# HD68_BNC_Breakout.net
KiCad netlist of a schematic drawn in Altium Designer
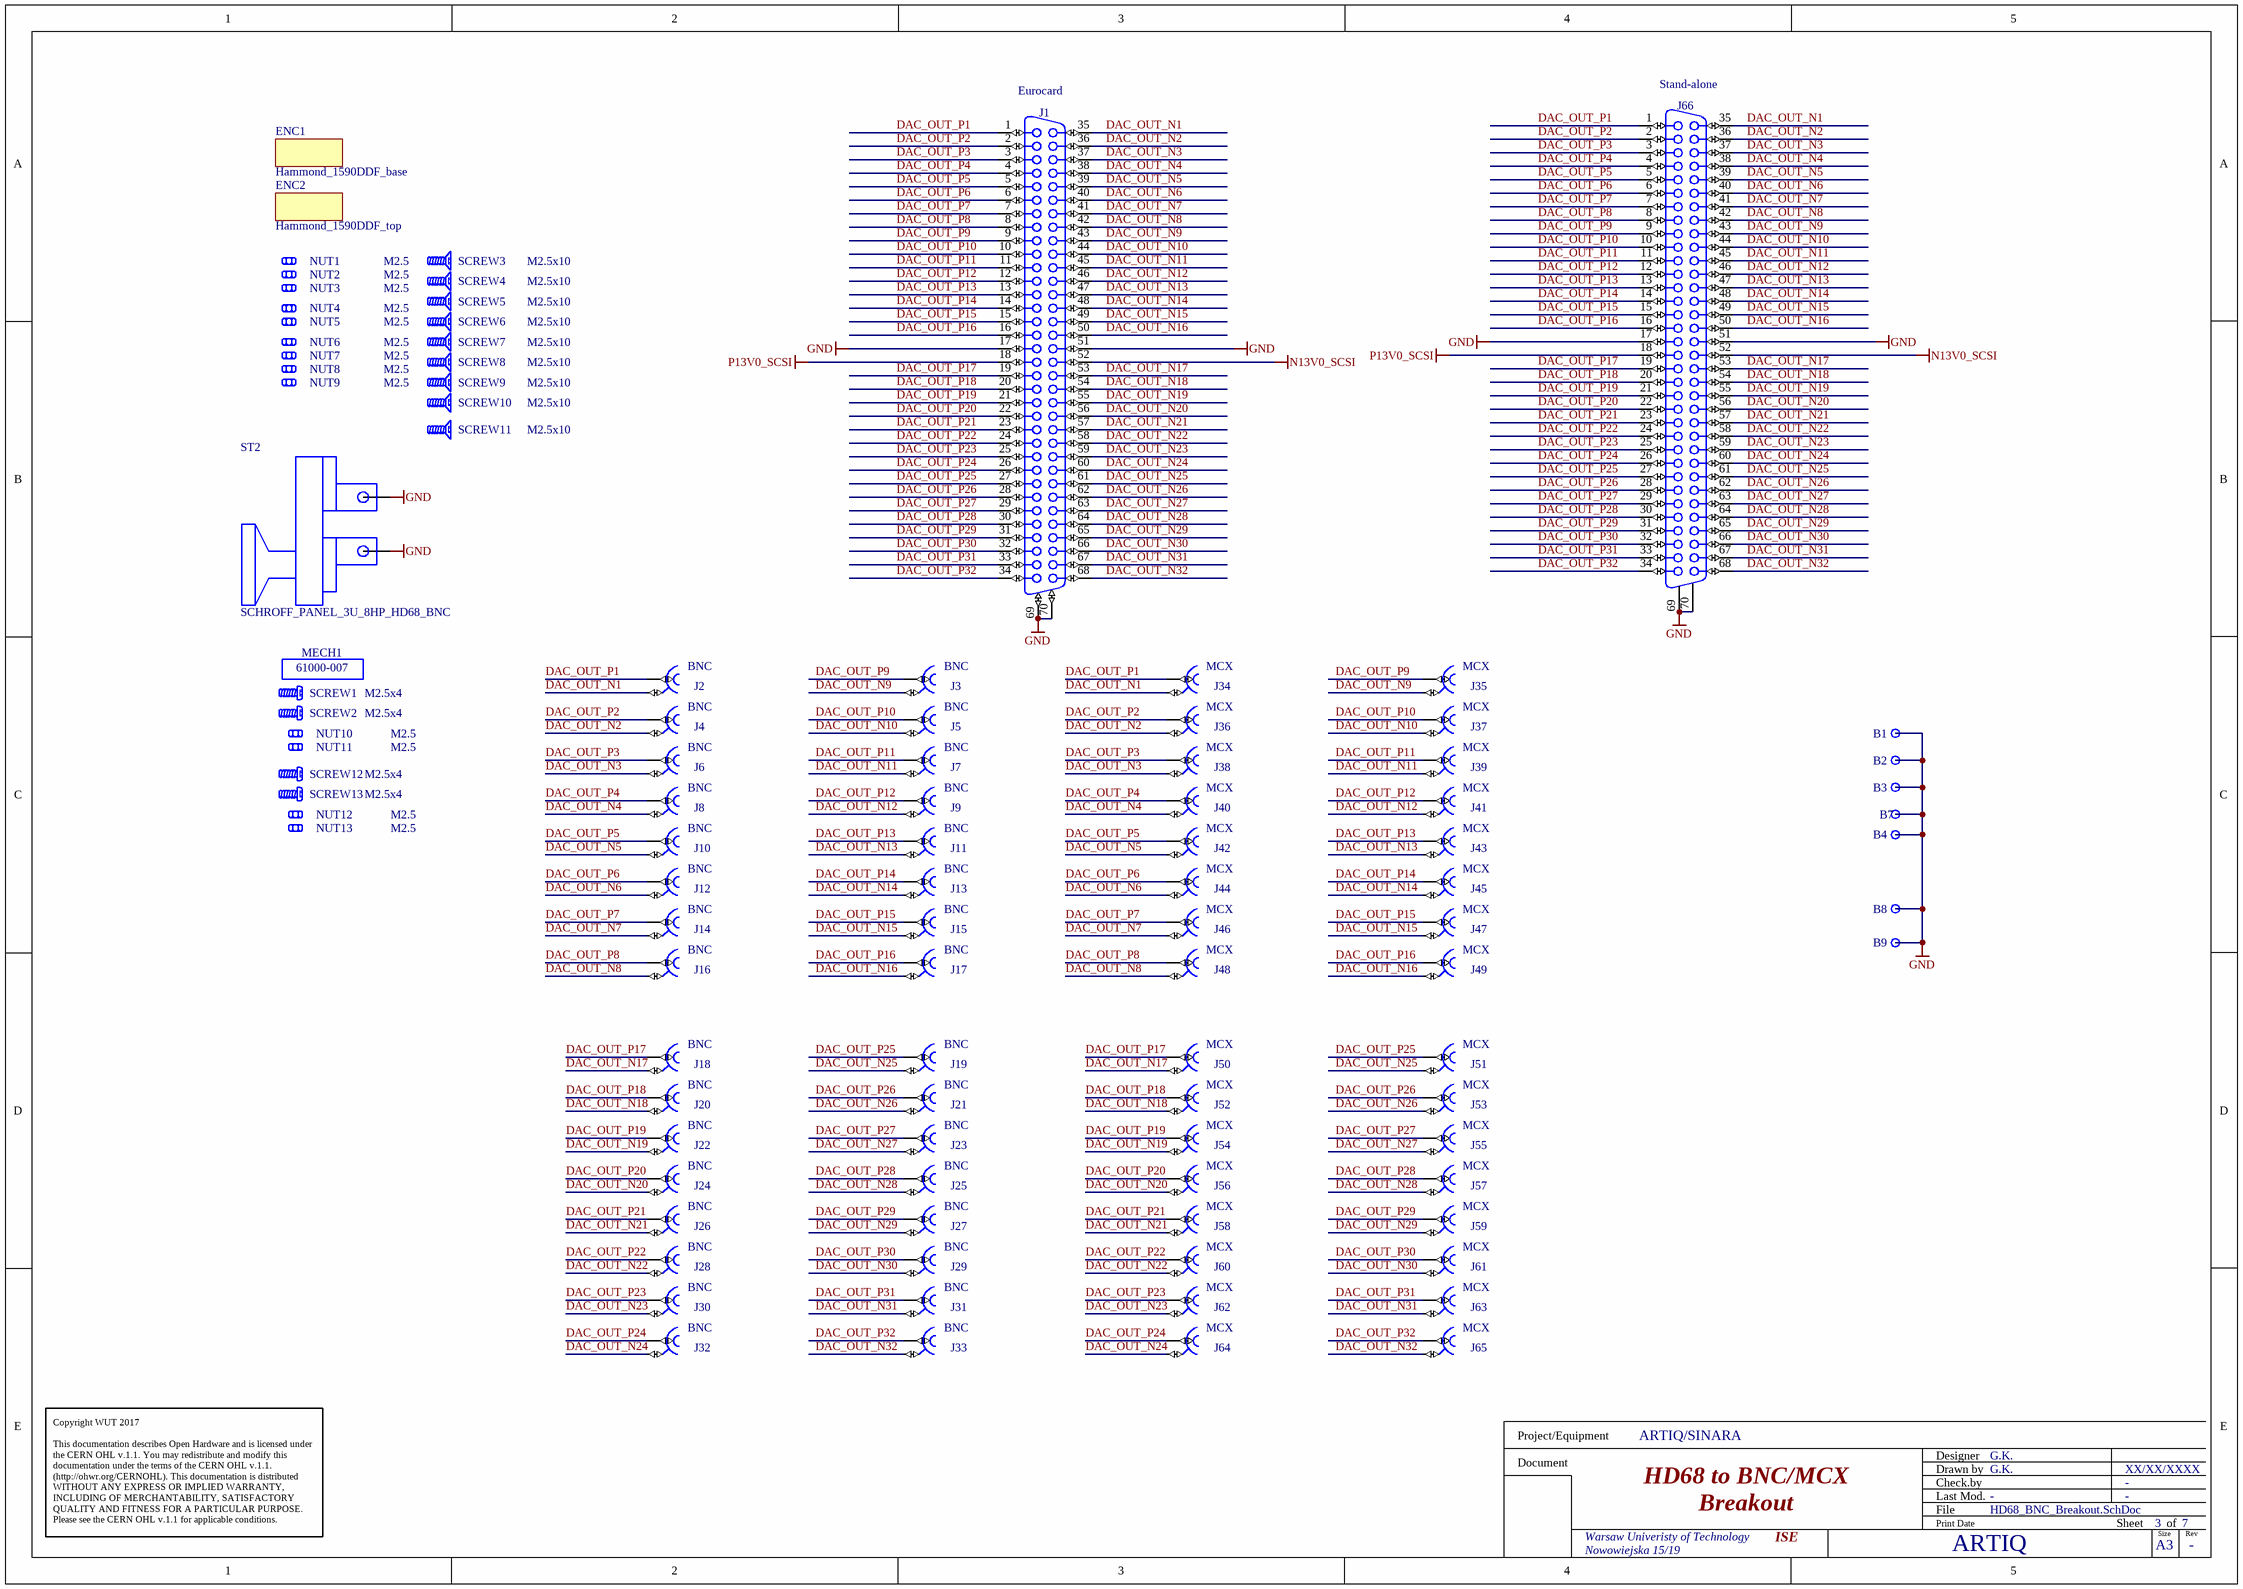
[diagram p0: HD68_BNC_Breakout.SchDoc]

(export (version "E")
  (design (tool "Eeschema 10.0.6"))
  (components
    (comp (ref "B1")
      (value "Plated Hole")
      (footprint "MTG270_500")
      (description "Single Terminal Socket")
      (fields (field (name "PART NUMBER") "PLATED_HOLE2.7_PAD5.0") (field (name "AUTHOR") "CERN DEM JMW"))
      (libsource (lib "Eletro-mechanical") (part "Single Terminal Socket"))
    )
    (comp (ref "B2")
      (value "Plated Hole")
      (footprint "MTG270_500")
      (description "Single Terminal Socket")
      (fields (field (name "PART NUMBER") "PLATED_HOLE2.7_PAD5.0") (field (name "AUTHOR") "CERN DEM JMW"))
      (libsource (lib "Eletro-mechanical") (part "Single Terminal Socket"))
    )
    (comp (ref "B3")
      (value "Plated Hole")
      (footprint "MTG270_500")
      (description "Single Terminal Socket")
      (fields (field (name "PART NUMBER") "PLATED_HOLE2.7_PAD5.0") (field (name "AUTHOR") "CERN DEM JMW"))
      (libsource (lib "Eletro-mechanical") (part "Single Terminal Socket"))
    )
    (comp (ref "B4")
      (value "Plated Hole")
      (footprint "MTG270_500")
      (description "Single Terminal Socket")
      (fields (field (name "PART NUMBER") "PLATED_HOLE2.7_PAD5.0") (field (name "AUTHOR") "CERN DEM JMW"))
      (libsource (lib "Eletro-mechanical") (part "Single Terminal Socket"))
    )
    (comp (ref "B7")
      (value "Plated Hole")
      (footprint "MTG270_500")
      (description "Single Terminal Socket")
      (fields (field (name "PART NUMBER") "PLATED_HOLE2.7_PAD5.0") (field (name "AUTHOR") "CERN DEM JMW"))
      (libsource (lib "Eletro-mechanical") (part "Single Terminal Socket"))
    )
    (comp (ref "B8")
      (value "Plated Hole")
      (footprint "MTG270_500")
      (description "Single Terminal Socket")
      (fields (field (name "PART NUMBER") "PLATED_HOLE2.7_PAD5.0") (field (name "AUTHOR") "CERN DEM JMW"))
      (libsource (lib "Eletro-mechanical") (part "Single Terminal Socket"))
    )
    (comp (ref "B9")
      (value "Plated Hole")
      (footprint "MTG270_500")
      (description "Single Terminal Socket")
      (fields (field (name "PART NUMBER") "PLATED_HOLE2.7_PAD5.0") (field (name "AUTHOR") "CERN DEM JMW"))
      (libsource (lib "Eletro-mechanical") (part "Single Terminal Socket"))
    )
    (comp (ref "ENC1")
      (value "Hammond_1590DDF_base")
      (footprint "1590DDF_base")
      (description "Hammond 1590DDF enclosure base part")
      (libsource (lib "Mechanical") (part "Hammond_1590DDF_base"))
    )
    (comp (ref "ENC2")
      (value "Hammond_1590DDF_top")
      (footprint "1590D-DD-E_LID_custom")
      (description "Hammond 1590DDF enclosure lid with custom cutouts")
      (libsource (lib "Mechanical") (part "Hammond_1590DDF_top_custom"))
    )
    (comp (ref "J1")
      (value "D-SUB")
      (footprint "TYCO_5787082-7")
      (description "68 contacts, AMPLIMITE .050\", Right Angled Receptacle Series III")
      (fields
        (field (name "PART NUMBER") "TYCO_5787082-7")
        (field (name "MANUFACTURER") "TYCO ELECTRONICS")
        (field (name "AUTHOR") "CERN DEM JLC")
      )
      (libsource (lib "Connectors") (part "TYCO_5787082-7"))
    )
    (comp (ref "J2")
      (value "BNC")
      (footprint "TYCO_5-1634506-1")
      (fields
        (field (name "PART NUMBER") "TYCO_5-1634506-1")
        (field (name "MANUFACTURER") "TYCO ELECTRONICS")
        (field (name "MANUFACTURER PART NUMBER") "5-1634506-1")
        (field (name "AUTHOR") "CERN DEM JLC")
      )
      (libsource (lib "Connectors") (part "Coax_1Female_1Shield"))
    )
    (comp (ref "J3")
      (value "BNC")
      (footprint "TYCO_5-1634506-1")
      (fields
        (field (name "PART NUMBER") "TYCO_5-1634506-1")
        (field (name "MANUFACTURER") "TYCO ELECTRONICS")
        (field (name "MANUFACTURER PART NUMBER") "5-1634506-1")
        (field (name "AUTHOR") "CERN DEM JLC")
      )
      (libsource (lib "Connectors") (part "Coax_1Female_1Shield"))
    )
    (comp (ref "J4")
      (value "BNC")
      (footprint "TYCO_5-1634506-1")
      (fields
        (field (name "PART NUMBER") "TYCO_5-1634506-1")
        (field (name "MANUFACTURER") "TYCO ELECTRONICS")
        (field (name "MANUFACTURER PART NUMBER") "5-1634506-1")
        (field (name "AUTHOR") "CERN DEM JLC")
      )
      (libsource (lib "Connectors") (part "Coax_1Female_1Shield"))
    )
    (comp (ref "J5")
      (value "BNC")
      (footprint "TYCO_5-1634506-1")
      (fields
        (field (name "PART NUMBER") "TYCO_5-1634506-1")
        (field (name "MANUFACTURER") "TYCO ELECTRONICS")
        (field (name "MANUFACTURER PART NUMBER") "5-1634506-1")
        (field (name "AUTHOR") "CERN DEM JLC")
      )
      (libsource (lib "Connectors") (part "Coax_1Female_1Shield"))
    )
    (comp (ref "J6")
      (value "BNC")
      (footprint "TYCO_5-1634506-1")
      (fields
        (field (name "PART NUMBER") "TYCO_5-1634506-1")
        (field (name "MANUFACTURER") "TYCO ELECTRONICS")
        (field (name "MANUFACTURER PART NUMBER") "5-1634506-1")
        (field (name "AUTHOR") "CERN DEM JLC")
      )
      (libsource (lib "Connectors") (part "Coax_1Female_1Shield"))
    )
    (comp (ref "J7")
      (value "BNC")
      (footprint "TYCO_5-1634506-1")
      (fields
        (field (name "PART NUMBER") "TYCO_5-1634506-1")
        (field (name "MANUFACTURER") "TYCO ELECTRONICS")
        (field (name "MANUFACTURER PART NUMBER") "5-1634506-1")
        (field (name "AUTHOR") "CERN DEM JLC")
      )
      (libsource (lib "Connectors") (part "Coax_1Female_1Shield"))
    )
    (comp (ref "J8")
      (value "BNC")
      (footprint "TYCO_5-1634506-1")
      (fields
        (field (name "PART NUMBER") "TYCO_5-1634506-1")
        (field (name "MANUFACTURER") "TYCO ELECTRONICS")
        (field (name "MANUFACTURER PART NUMBER") "5-1634506-1")
        (field (name "AUTHOR") "CERN DEM JLC")
      )
      (libsource (lib "Connectors") (part "Coax_1Female_1Shield"))
    )
    (comp (ref "J9")
      (value "BNC")
      (footprint "TYCO_5-1634506-1")
      (fields
        (field (name "PART NUMBER") "TYCO_5-1634506-1")
        (field (name "MANUFACTURER") "TYCO ELECTRONICS")
        (field (name "MANUFACTURER PART NUMBER") "5-1634506-1")
        (field (name "AUTHOR") "CERN DEM JLC")
      )
      (libsource (lib "Connectors") (part "Coax_1Female_1Shield"))
    )
    (comp (ref "J10")
      (value "BNC")
      (footprint "TYCO_5-1634506-1")
      (fields
        (field (name "PART NUMBER") "TYCO_5-1634506-1")
        (field (name "MANUFACTURER") "TYCO ELECTRONICS")
        (field (name "MANUFACTURER PART NUMBER") "5-1634506-1")
        (field (name "AUTHOR") "CERN DEM JLC")
      )
      (libsource (lib "Connectors") (part "Coax_1Female_1Shield"))
    )
    (comp (ref "J11")
      (value "BNC")
      (footprint "TYCO_5-1634506-1")
      (fields
        (field (name "PART NUMBER") "TYCO_5-1634506-1")
        (field (name "MANUFACTURER") "TYCO ELECTRONICS")
        (field (name "MANUFACTURER PART NUMBER") "5-1634506-1")
        (field (name "AUTHOR") "CERN DEM JLC")
      )
      (libsource (lib "Connectors") (part "Coax_1Female_1Shield"))
    )
    (comp (ref "J12")
      (value "BNC")
      (footprint "TYCO_5-1634506-1")
      (fields
        (field (name "PART NUMBER") "TYCO_5-1634506-1")
        (field (name "MANUFACTURER") "TYCO ELECTRONICS")
        (field (name "MANUFACTURER PART NUMBER") "5-1634506-1")
        (field (name "AUTHOR") "CERN DEM JLC")
      )
      (libsource (lib "Connectors") (part "Coax_1Female_1Shield"))
    )
    (comp (ref "J13")
      (value "BNC")
      (footprint "TYCO_5-1634506-1")
      (fields
        (field (name "PART NUMBER") "TYCO_5-1634506-1")
        (field (name "MANUFACTURER") "TYCO ELECTRONICS")
        (field (name "MANUFACTURER PART NUMBER") "5-1634506-1")
        (field (name "AUTHOR") "CERN DEM JLC")
      )
      (libsource (lib "Connectors") (part "Coax_1Female_1Shield"))
    )
    (comp (ref "J14")
      (value "BNC")
      (footprint "TYCO_5-1634506-1")
      (fields
        (field (name "PART NUMBER") "TYCO_5-1634506-1")
        (field (name "MANUFACTURER") "TYCO ELECTRONICS")
        (field (name "MANUFACTURER PART NUMBER") "5-1634506-1")
        (field (name "AUTHOR") "CERN DEM JLC")
      )
      (libsource (lib "Connectors") (part "Coax_1Female_1Shield"))
    )
    (comp (ref "J15")
      (value "BNC")
      (footprint "TYCO_5-1634506-1")
      (fields
        (field (name "PART NUMBER") "TYCO_5-1634506-1")
        (field (name "MANUFACTURER") "TYCO ELECTRONICS")
        (field (name "MANUFACTURER PART NUMBER") "5-1634506-1")
        (field (name "AUTHOR") "CERN DEM JLC")
      )
      (libsource (lib "Connectors") (part "Coax_1Female_1Shield"))
    )
    (comp (ref "J16")
      (value "BNC")
      (footprint "TYCO_5-1634506-1")
      (fields
        (field (name "PART NUMBER") "TYCO_5-1634506-1")
        (field (name "MANUFACTURER") "TYCO ELECTRONICS")
        (field (name "MANUFACTURER PART NUMBER") "5-1634506-1")
        (field (name "AUTHOR") "CERN DEM JLC")
      )
      (libsource (lib "Connectors") (part "Coax_1Female_1Shield"))
    )
    (comp (ref "J17")
      (value "BNC")
      (footprint "TYCO_5-1634506-1")
      (fields
        (field (name "PART NUMBER") "TYCO_5-1634506-1")
        (field (name "MANUFACTURER") "TYCO ELECTRONICS")
        (field (name "MANUFACTURER PART NUMBER") "5-1634506-1")
        (field (name "AUTHOR") "CERN DEM JLC")
      )
      (libsource (lib "Connectors") (part "Coax_1Female_1Shield"))
    )
    (comp (ref "J18")
      (value "BNC")
      (footprint "TYCO_5-1634506-1")
      (fields
        (field (name "PART NUMBER") "TYCO_5-1634506-1")
        (field (name "MANUFACTURER") "TYCO ELECTRONICS")
        (field (name "MANUFACTURER PART NUMBER") "5-1634506-1")
        (field (name "AUTHOR") "CERN DEM JLC")
      )
      (libsource (lib "Connectors") (part "Coax_1Female_1Shield"))
    )
    (comp (ref "J19")
      (value "BNC")
      (footprint "TYCO_5-1634506-1")
      (fields
        (field (name "PART NUMBER") "TYCO_5-1634506-1")
        (field (name "MANUFACTURER") "TYCO ELECTRONICS")
        (field (name "MANUFACTURER PART NUMBER") "5-1634506-1")
        (field (name "AUTHOR") "CERN DEM JLC")
      )
      (libsource (lib "Connectors") (part "Coax_1Female_1Shield"))
    )
    (comp (ref "J20")
      (value "BNC")
      (footprint "TYCO_5-1634506-1")
      (fields
        (field (name "PART NUMBER") "TYCO_5-1634506-1")
        (field (name "MANUFACTURER") "TYCO ELECTRONICS")
        (field (name "MANUFACTURER PART NUMBER") "5-1634506-1")
        (field (name "AUTHOR") "CERN DEM JLC")
      )
      (libsource (lib "Connectors") (part "Coax_1Female_1Shield"))
    )
    (comp (ref "J21")
      (value "BNC")
      (footprint "TYCO_5-1634506-1")
      (fields
        (field (name "PART NUMBER") "TYCO_5-1634506-1")
        (field (name "MANUFACTURER") "TYCO ELECTRONICS")
        (field (name "MANUFACTURER PART NUMBER") "5-1634506-1")
        (field (name "AUTHOR") "CERN DEM JLC")
      )
      (libsource (lib "Connectors") (part "Coax_1Female_1Shield"))
    )
    (comp (ref "J22")
      (value "BNC")
      (footprint "TYCO_5-1634506-1")
      (fields
        (field (name "PART NUMBER") "TYCO_5-1634506-1")
        (field (name "MANUFACTURER") "TYCO ELECTRONICS")
        (field (name "MANUFACTURER PART NUMBER") "5-1634506-1")
        (field (name "AUTHOR") "CERN DEM JLC")
      )
      (libsource (lib "Connectors") (part "Coax_1Female_1Shield"))
    )
    (comp (ref "J23")
      (value "BNC")
      (footprint "TYCO_5-1634506-1")
      (fields
        (field (name "PART NUMBER") "TYCO_5-1634506-1")
        (field (name "MANUFACTURER") "TYCO ELECTRONICS")
        (field (name "MANUFACTURER PART NUMBER") "5-1634506-1")
        (field (name "AUTHOR") "CERN DEM JLC")
      )
      (libsource (lib "Connectors") (part "Coax_1Female_1Shield"))
    )
    (comp (ref "J24")
      (value "BNC")
      (footprint "TYCO_5-1634506-1")
      (fields
        (field (name "PART NUMBER") "TYCO_5-1634506-1")
        (field (name "MANUFACTURER") "TYCO ELECTRONICS")
        (field (name "MANUFACTURER PART NUMBER") "5-1634506-1")
        (field (name "AUTHOR") "CERN DEM JLC")
      )
      (libsource (lib "Connectors") (part "Coax_1Female_1Shield"))
    )
    (comp (ref "J25")
      (value "BNC")
      (footprint "TYCO_5-1634506-1")
      (fields
        (field (name "PART NUMBER") "TYCO_5-1634506-1")
        (field (name "MANUFACTURER") "TYCO ELECTRONICS")
        (field (name "MANUFACTURER PART NUMBER") "5-1634506-1")
        (field (name "AUTHOR") "CERN DEM JLC")
      )
      (libsource (lib "Connectors") (part "Coax_1Female_1Shield"))
    )
    (comp (ref "J26")
      (value "BNC")
      (footprint "TYCO_5-1634506-1")
      (fields
        (field (name "PART NUMBER") "TYCO_5-1634506-1")
        (field (name "MANUFACTURER") "TYCO ELECTRONICS")
        (field (name "MANUFACTURER PART NUMBER") "5-1634506-1")
        (field (name "AUTHOR") "CERN DEM JLC")
      )
      (libsource (lib "Connectors") (part "Coax_1Female_1Shield"))
    )
    (comp (ref "J27")
      (value "BNC")
      (footprint "TYCO_5-1634506-1")
      (fields
        (field (name "PART NUMBER") "TYCO_5-1634506-1")
        (field (name "MANUFACTURER") "TYCO ELECTRONICS")
        (field (name "MANUFACTURER PART NUMBER") "5-1634506-1")
        (field (name "AUTHOR") "CERN DEM JLC")
      )
      (libsource (lib "Connectors") (part "Coax_1Female_1Shield"))
    )
    (comp (ref "J28")
      (value "BNC")
      (footprint "TYCO_5-1634506-1")
      (fields
        (field (name "PART NUMBER") "TYCO_5-1634506-1")
        (field (name "MANUFACTURER") "TYCO ELECTRONICS")
        (field (name "MANUFACTURER PART NUMBER") "5-1634506-1")
        (field (name "AUTHOR") "CERN DEM JLC")
      )
      (libsource (lib "Connectors") (part "Coax_1Female_1Shield"))
    )
    (comp (ref "J29")
      (value "BNC")
      (footprint "TYCO_5-1634506-1")
      (fields
        (field (name "PART NUMBER") "TYCO_5-1634506-1")
        (field (name "MANUFACTURER") "TYCO ELECTRONICS")
        (field (name "MANUFACTURER PART NUMBER") "5-1634506-1")
        (field (name "AUTHOR") "CERN DEM JLC")
      )
      (libsource (lib "Connectors") (part "Coax_1Female_1Shield"))
    )
    (comp (ref "J30")
      (value "BNC")
      (footprint "TYCO_5-1634506-1")
      (fields
        (field (name "PART NUMBER") "TYCO_5-1634506-1")
        (field (name "MANUFACTURER") "TYCO ELECTRONICS")
        (field (name "MANUFACTURER PART NUMBER") "5-1634506-1")
        (field (name "AUTHOR") "CERN DEM JLC")
      )
      (libsource (lib "Connectors") (part "Coax_1Female_1Shield"))
    )
    (comp (ref "J31")
      (value "BNC")
      (footprint "TYCO_5-1634506-1")
      (fields
        (field (name "PART NUMBER") "TYCO_5-1634506-1")
        (field (name "MANUFACTURER") "TYCO ELECTRONICS")
        (field (name "MANUFACTURER PART NUMBER") "5-1634506-1")
        (field (name "AUTHOR") "CERN DEM JLC")
      )
      (libsource (lib "Connectors") (part "Coax_1Female_1Shield"))
    )
    (comp (ref "J32")
      (value "BNC")
      (footprint "TYCO_5-1634506-1")
      (fields
        (field (name "PART NUMBER") "TYCO_5-1634506-1")
        (field (name "MANUFACTURER") "TYCO ELECTRONICS")
        (field (name "MANUFACTURER PART NUMBER") "5-1634506-1")
        (field (name "AUTHOR") "CERN DEM JLC")
      )
      (libsource (lib "Connectors") (part "Coax_1Female_1Shield"))
    )
    (comp (ref "J33")
      (value "BNC")
      (footprint "TYCO_5-1634506-1")
      (fields
        (field (name "PART NUMBER") "TYCO_5-1634506-1")
        (field (name "MANUFACTURER") "TYCO ELECTRONICS")
        (field (name "MANUFACTURER PART NUMBER") "5-1634506-1")
        (field (name "AUTHOR") "CERN DEM JLC")
      )
      (libsource (lib "Connectors") (part "Coax_1Female_1Shield"))
    )
    (comp (ref "J34")
      (value "MCX")
      (footprint "AMPHENOL_919-109J-51PX")
      (fields
        (field (name "PART NUMBER") "AMPHENOL_919-109J-51PX")
        (field (name "MANUFACTURER") "AMPHENOL")
        (field (name "MANUFACTURER PART NUMBER") "919-109J-51PX (MCX6251B1-3GT30G-50)")
        (field (name "AUTHOR") "CERN DEM BC")
      )
      (libsource (lib "Connectors") (part "Coax_1Female_1Shield"))
    )
    (comp (ref "J35")
      (value "MCX")
      (footprint "AMPHENOL_919-109J-51PX")
      (fields
        (field (name "PART NUMBER") "AMPHENOL_919-109J-51PX")
        (field (name "MANUFACTURER") "AMPHENOL")
        (field (name "MANUFACTURER PART NUMBER") "919-109J-51PX (MCX6251B1-3GT30G-50)")
        (field (name "AUTHOR") "CERN DEM BC")
      )
      (libsource (lib "Connectors") (part "Coax_1Female_1Shield"))
    )
    (comp (ref "J36")
      (value "MCX")
      (footprint "AMPHENOL_919-109J-51PX")
      (fields
        (field (name "PART NUMBER") "AMPHENOL_919-109J-51PX")
        (field (name "MANUFACTURER") "AMPHENOL")
        (field (name "MANUFACTURER PART NUMBER") "919-109J-51PX (MCX6251B1-3GT30G-50)")
        (field (name "AUTHOR") "CERN DEM BC")
      )
      (libsource (lib "Connectors") (part "Coax_1Female_1Shield"))
    )
    (comp (ref "J37")
      (value "MCX")
      (footprint "AMPHENOL_919-109J-51PX")
      (fields
        (field (name "PART NUMBER") "AMPHENOL_919-109J-51PX")
        (field (name "MANUFACTURER") "AMPHENOL")
        (field (name "MANUFACTURER PART NUMBER") "919-109J-51PX (MCX6251B1-3GT30G-50)")
        (field (name "AUTHOR") "CERN DEM BC")
      )
      (libsource (lib "Connectors") (part "Coax_1Female_1Shield"))
    )
    (comp (ref "J38")
      (value "MCX")
      (footprint "AMPHENOL_919-109J-51PX")
      (fields
        (field (name "PART NUMBER") "AMPHENOL_919-109J-51PX")
        (field (name "MANUFACTURER") "AMPHENOL")
        (field (name "MANUFACTURER PART NUMBER") "919-109J-51PX (MCX6251B1-3GT30G-50)")
        (field (name "AUTHOR") "CERN DEM BC")
      )
      (libsource (lib "Connectors") (part "Coax_1Female_1Shield"))
    )
    (comp (ref "J39")
      (value "MCX")
      (footprint "AMPHENOL_919-109J-51PX")
      (fields
        (field (name "PART NUMBER") "AMPHENOL_919-109J-51PX")
        (field (name "MANUFACTURER") "AMPHENOL")
        (field (name "MANUFACTURER PART NUMBER") "919-109J-51PX (MCX6251B1-3GT30G-50)")
        (field (name "AUTHOR") "CERN DEM BC")
      )
      (libsource (lib "Connectors") (part "Coax_1Female_1Shield"))
    )
    (comp (ref "J40")
      (value "MCX")
      (footprint "AMPHENOL_919-109J-51PX")
      (fields
        (field (name "PART NUMBER") "AMPHENOL_919-109J-51PX")
        (field (name "MANUFACTURER") "AMPHENOL")
        (field (name "MANUFACTURER PART NUMBER") "919-109J-51PX (MCX6251B1-3GT30G-50)")
        (field (name "AUTHOR") "CERN DEM BC")
      )
      (libsource (lib "Connectors") (part "Coax_1Female_1Shield"))
    )
    (comp (ref "J41")
      (value "MCX")
      (footprint "AMPHENOL_919-109J-51PX")
      (fields
        (field (name "PART NUMBER") "AMPHENOL_919-109J-51PX")
        (field (name "MANUFACTURER") "AMPHENOL")
        (field (name "MANUFACTURER PART NUMBER") "919-109J-51PX (MCX6251B1-3GT30G-50)")
        (field (name "AUTHOR") "CERN DEM BC")
      )
      (libsource (lib "Connectors") (part "Coax_1Female_1Shield"))
    )
    (comp (ref "J42")
      (value "MCX")
      (footprint "AMPHENOL_919-109J-51PX")
      (fields
        (field (name "PART NUMBER") "AMPHENOL_919-109J-51PX")
        (field (name "MANUFACTURER") "AMPHENOL")
        (field (name "MANUFACTURER PART NUMBER") "919-109J-51PX (MCX6251B1-3GT30G-50)")
        (field (name "AUTHOR") "CERN DEM BC")
      )
      (libsource (lib "Connectors") (part "Coax_1Female_1Shield"))
    )
    (comp (ref "J43")
      (value "MCX")
      (footprint "AMPHENOL_919-109J-51PX")
      (fields
        (field (name "PART NUMBER") "AMPHENOL_919-109J-51PX")
        (field (name "MANUFACTURER") "AMPHENOL")
        (field (name "MANUFACTURER PART NUMBER") "919-109J-51PX (MCX6251B1-3GT30G-50)")
        (field (name "AUTHOR") "CERN DEM BC")
      )
      (libsource (lib "Connectors") (part "Coax_1Female_1Shield"))
    )
    (comp (ref "J44")
      (value "MCX")
      (footprint "AMPHENOL_919-109J-51PX")
      (fields
        (field (name "PART NUMBER") "AMPHENOL_919-109J-51PX")
        (field (name "MANUFACTURER") "AMPHENOL")
        (field (name "MANUFACTURER PART NUMBER") "919-109J-51PX (MCX6251B1-3GT30G-50)")
        (field (name "AUTHOR") "CERN DEM BC")
      )
      (libsource (lib "Connectors") (part "Coax_1Female_1Shield"))
    )
    (comp (ref "J45")
      (value "MCX")
      (footprint "AMPHENOL_919-109J-51PX")
      (fields
        (field (name "PART NUMBER") "AMPHENOL_919-109J-51PX")
        (field (name "MANUFACTURER") "AMPHENOL")
        (field (name "MANUFACTURER PART NUMBER") "919-109J-51PX (MCX6251B1-3GT30G-50)")
        (field (name "AUTHOR") "CERN DEM BC")
      )
      (libsource (lib "Connectors") (part "Coax_1Female_1Shield"))
    )
    (comp (ref "J46")
      (value "MCX")
      (footprint "AMPHENOL_919-109J-51PX")
      (fields
        (field (name "PART NUMBER") "AMPHENOL_919-109J-51PX")
        (field (name "MANUFACTURER") "AMPHENOL")
        (field (name "MANUFACTURER PART NUMBER") "919-109J-51PX (MCX6251B1-3GT30G-50)")
        (field (name "AUTHOR") "CERN DEM BC")
      )
      (libsource (lib "Connectors") (part "Coax_1Female_1Shield"))
    )
    (comp (ref "J47")
      (value "MCX")
      (footprint "AMPHENOL_919-109J-51PX")
      (fields
        (field (name "PART NUMBER") "AMPHENOL_919-109J-51PX")
        (field (name "MANUFACTURER") "AMPHENOL")
        (field (name "MANUFACTURER PART NUMBER") "919-109J-51PX (MCX6251B1-3GT30G-50)")
        (field (name "AUTHOR") "CERN DEM BC")
      )
      (libsource (lib "Connectors") (part "Coax_1Female_1Shield"))
    )
    (comp (ref "J48")
      (value "MCX")
      (footprint "AMPHENOL_919-109J-51PX")
      (fields
        (field (name "PART NUMBER") "AMPHENOL_919-109J-51PX")
        (field (name "MANUFACTURER") "AMPHENOL")
        (field (name "MANUFACTURER PART NUMBER") "919-109J-51PX (MCX6251B1-3GT30G-50)")
        (field (name "AUTHOR") "CERN DEM BC")
      )
      (libsource (lib "Connectors") (part "Coax_1Female_1Shield"))
    )
    (comp (ref "J49")
      (value "MCX")
      (footprint "AMPHENOL_919-109J-51PX")
      (fields
        (field (name "PART NUMBER") "AMPHENOL_919-109J-51PX")
        (field (name "MANUFACTURER") "AMPHENOL")
        (field (name "MANUFACTURER PART NUMBER") "919-109J-51PX (MCX6251B1-3GT30G-50)")
        (field (name "AUTHOR") "CERN DEM BC")
      )
      (libsource (lib "Connectors") (part "Coax_1Female_1Shield"))
    )
    (comp (ref "J50")
      (value "MCX")
      (footprint "AMPHENOL_919-109J-51PX")
      (fields
        (field (name "PART NUMBER") "AMPHENOL_919-109J-51PX")
        (field (name "MANUFACTURER") "AMPHENOL")
        (field (name "MANUFACTURER PART NUMBER") "919-109J-51PX (MCX6251B1-3GT30G-50)")
        (field (name "AUTHOR") "CERN DEM BC")
      )
      (libsource (lib "Connectors") (part "Coax_1Female_1Shield"))
    )
    (comp (ref "J51")
      (value "MCX")
      (footprint "AMPHENOL_919-109J-51PX")
      (fields
        (field (name "PART NUMBER") "AMPHENOL_919-109J-51PX")
        (field (name "MANUFACTURER") "AMPHENOL")
        (field (name "MANUFACTURER PART NUMBER") "919-109J-51PX (MCX6251B1-3GT30G-50)")
        (field (name "AUTHOR") "CERN DEM BC")
      )
      (libsource (lib "Connectors") (part "Coax_1Female_1Shield"))
    )
    (comp (ref "J52")
      (value "MCX")
      (footprint "AMPHENOL_919-109J-51PX")
      (fields
        (field (name "PART NUMBER") "AMPHENOL_919-109J-51PX")
        (field (name "MANUFACTURER") "AMPHENOL")
        (field (name "MANUFACTURER PART NUMBER") "919-109J-51PX (MCX6251B1-3GT30G-50)")
        (field (name "AUTHOR") "CERN DEM BC")
      )
      (libsource (lib "Connectors") (part "Coax_1Female_1Shield"))
    )
    (comp (ref "J53")
      (value "MCX")
      (footprint "AMPHENOL_919-109J-51PX")
      (fields
        (field (name "PART NUMBER") "AMPHENOL_919-109J-51PX")
        (field (name "MANUFACTURER") "AMPHENOL")
        (field (name "MANUFACTURER PART NUMBER") "919-109J-51PX (MCX6251B1-3GT30G-50)")
        (field (name "AUTHOR") "CERN DEM BC")
      )
      (libsource (lib "Connectors") (part "Coax_1Female_1Shield"))
    )
    (comp (ref "J54")
      (value "MCX")
      (footprint "AMPHENOL_919-109J-51PX")
      (fields
        (field (name "PART NUMBER") "AMPHENOL_919-109J-51PX")
        (field (name "MANUFACTURER") "AMPHENOL")
        (field (name "MANUFACTURER PART NUMBER") "919-109J-51PX (MCX6251B1-3GT30G-50)")
        (field (name "AUTHOR") "CERN DEM BC")
      )
      (libsource (lib "Connectors") (part "Coax_1Female_1Shield"))
    )
    (comp (ref "J55")
      (value "MCX")
      (footprint "AMPHENOL_919-109J-51PX")
      (fields
        (field (name "PART NUMBER") "AMPHENOL_919-109J-51PX")
        (field (name "MANUFACTURER") "AMPHENOL")
        (field (name "MANUFACTURER PART NUMBER") "919-109J-51PX (MCX6251B1-3GT30G-50)")
        (field (name "AUTHOR") "CERN DEM BC")
      )
      (libsource (lib "Connectors") (part "Coax_1Female_1Shield"))
    )
    (comp (ref "J56")
      (value "MCX")
      (footprint "AMPHENOL_919-109J-51PX")
      (fields
        (field (name "PART NUMBER") "AMPHENOL_919-109J-51PX")
        (field (name "MANUFACTURER") "AMPHENOL")
        (field (name "MANUFACTURER PART NUMBER") "919-109J-51PX (MCX6251B1-3GT30G-50)")
        (field (name "AUTHOR") "CERN DEM BC")
      )
      (libsource (lib "Connectors") (part "Coax_1Female_1Shield"))
    )
    (comp (ref "J57")
      (value "MCX")
      (footprint "AMPHENOL_919-109J-51PX")
      (fields
        (field (name "PART NUMBER") "AMPHENOL_919-109J-51PX")
        (field (name "MANUFACTURER") "AMPHENOL")
        (field (name "MANUFACTURER PART NUMBER") "919-109J-51PX (MCX6251B1-3GT30G-50)")
        (field (name "AUTHOR") "CERN DEM BC")
      )
      (libsource (lib "Connectors") (part "Coax_1Female_1Shield"))
    )
    (comp (ref "J58")
      (value "MCX")
      (footprint "AMPHENOL_919-109J-51PX")
      (fields
        (field (name "PART NUMBER") "AMPHENOL_919-109J-51PX")
        (field (name "MANUFACTURER") "AMPHENOL")
        (field (name "MANUFACTURER PART NUMBER") "919-109J-51PX (MCX6251B1-3GT30G-50)")
        (field (name "AUTHOR") "CERN DEM BC")
      )
      (libsource (lib "Connectors") (part "Coax_1Female_1Shield"))
    )
    (comp (ref "J59")
      (value "MCX")
      (footprint "AMPHENOL_919-109J-51PX")
      (fields
        (field (name "PART NUMBER") "AMPHENOL_919-109J-51PX")
        (field (name "MANUFACTURER") "AMPHENOL")
        (field (name "MANUFACTURER PART NUMBER") "919-109J-51PX (MCX6251B1-3GT30G-50)")
        (field (name "AUTHOR") "CERN DEM BC")
      )
      (libsource (lib "Connectors") (part "Coax_1Female_1Shield"))
    )
    (comp (ref "J60")
      (value "MCX")
      (footprint "AMPHENOL_919-109J-51PX")
      (fields
        (field (name "PART NUMBER") "AMPHENOL_919-109J-51PX")
        (field (name "MANUFACTURER") "AMPHENOL")
        (field (name "MANUFACTURER PART NUMBER") "919-109J-51PX (MCX6251B1-3GT30G-50)")
        (field (name "AUTHOR") "CERN DEM BC")
      )
      (libsource (lib "Connectors") (part "Coax_1Female_1Shield"))
    )
    (comp (ref "J61")
      (value "MCX")
      (footprint "AMPHENOL_919-109J-51PX")
      (fields
        (field (name "PART NUMBER") "AMPHENOL_919-109J-51PX")
        (field (name "MANUFACTURER") "AMPHENOL")
        (field (name "MANUFACTURER PART NUMBER") "919-109J-51PX (MCX6251B1-3GT30G-50)")
        (field (name "AUTHOR") "CERN DEM BC")
      )
      (libsource (lib "Connectors") (part "Coax_1Female_1Shield"))
    )
    (comp (ref "J62")
      (value "MCX")
      (footprint "AMPHENOL_919-109J-51PX")
      (fields
        (field (name "PART NUMBER") "AMPHENOL_919-109J-51PX")
        (field (name "MANUFACTURER") "AMPHENOL")
        (field (name "MANUFACTURER PART NUMBER") "919-109J-51PX (MCX6251B1-3GT30G-50)")
        (field (name "AUTHOR") "CERN DEM BC")
      )
      (libsource (lib "Connectors") (part "Coax_1Female_1Shield"))
    )
    (comp (ref "J63")
      (value "MCX")
      (footprint "AMPHENOL_919-109J-51PX")
      (fields
        (field (name "PART NUMBER") "AMPHENOL_919-109J-51PX")
        (field (name "MANUFACTURER") "AMPHENOL")
        (field (name "MANUFACTURER PART NUMBER") "919-109J-51PX (MCX6251B1-3GT30G-50)")
        (field (name "AUTHOR") "CERN DEM BC")
      )
      (libsource (lib "Connectors") (part "Coax_1Female_1Shield"))
    )
    (comp (ref "J64")
      (value "MCX")
      (footprint "AMPHENOL_919-109J-51PX")
      (fields
        (field (name "PART NUMBER") "AMPHENOL_919-109J-51PX")
        (field (name "MANUFACTURER") "AMPHENOL")
        (field (name "MANUFACTURER PART NUMBER") "919-109J-51PX (MCX6251B1-3GT30G-50)")
        (field (name "AUTHOR") "CERN DEM BC")
      )
      (libsource (lib "Connectors") (part "Coax_1Female_1Shield"))
    )
    (comp (ref "J65")
      (value "MCX")
      (footprint "AMPHENOL_919-109J-51PX")
      (fields
        (field (name "PART NUMBER") "AMPHENOL_919-109J-51PX")
        (field (name "MANUFACTURER") "AMPHENOL")
        (field (name "MANUFACTURER PART NUMBER") "919-109J-51PX (MCX6251B1-3GT30G-50)")
        (field (name "AUTHOR") "CERN DEM BC")
      )
      (libsource (lib "Connectors") (part "Coax_1Female_1Shield"))
    )
    (comp (ref "J66")
      (value "AMPLIMITE")
      (footprint "TYCO_5749721-7")
      (description "AMPLIMITE .050 Series, 68 Positions Vertical Receptacle")
      (fields
        (field (name "PART NUMBER") "TYCO_5749721-7")
        (field (name "MANUFACTURER") "TYCO ELECTRONICS")
        (field (name "AUTHOR") "CERN DEM HF")
      )
      (libsource (lib "Connectors") (part "TYCO_5749721-7"))
    )
    (comp (ref "MECH1")
      (value "61000-007")
      (footprint "GENERIC_MECH")
      (description "PCB Solder Side Cover, 3 U, 100 mm x 160 mm, 55°C Schroff insulating plate")
      (fields (field (name "MANUFACTURER") "Schroff") (field (name "AUTHOR") "GK"))
      (libsource (lib "Mechanical") (part "Generic_mechanical"))
    )
    (comp (ref "NUT1")
      (value "M2.5")
      (footprint "BOSSARD_BN628-1241427_v")
      (description "Nut")
      (fields
        (field (name "PART NUMBER") "BOSSARD_BN628-1241427_v")
        (field (name "MANUFACTURER") "BOSSARD")
        (field (name "AUTHOR") "CERN DEM JMW")
      )
      (libsource (lib "Eletro-mechanical") (part "Nut"))
    )
    (comp (ref "NUT2")
      (value "M2.5")
      (footprint "BOSSARD_BN628-1241427_v")
      (description "Nut")
      (fields
        (field (name "PART NUMBER") "BOSSARD_BN628-1241427_v")
        (field (name "MANUFACTURER") "BOSSARD")
        (field (name "AUTHOR") "CERN DEM JMW")
      )
      (libsource (lib "Eletro-mechanical") (part "Nut"))
    )
    (comp (ref "NUT3")
      (value "M2.5")
      (footprint "BOSSARD_BN628-1241427_v")
      (description "Nut")
      (fields
        (field (name "PART NUMBER") "BOSSARD_BN628-1241427_v")
        (field (name "MANUFACTURER") "BOSSARD")
        (field (name "AUTHOR") "CERN DEM JMW")
      )
      (libsource (lib "Eletro-mechanical") (part "Nut"))
    )
    (comp (ref "NUT4")
      (value "M2.5")
      (footprint "BOSSARD_BN628-1241427_v")
      (description "Nut")
      (fields
        (field (name "PART NUMBER") "BOSSARD_BN628-1241427_v")
        (field (name "MANUFACTURER") "BOSSARD")
        (field (name "AUTHOR") "CERN DEM JMW")
      )
      (libsource (lib "Eletro-mechanical") (part "Nut"))
    )
    (comp (ref "NUT5")
      (value "M2.5")
      (footprint "BOSSARD_BN628-1241427_v")
      (description "Nut")
      (fields
        (field (name "PART NUMBER") "BOSSARD_BN628-1241427_v")
        (field (name "MANUFACTURER") "BOSSARD")
        (field (name "AUTHOR") "CERN DEM JMW")
      )
      (libsource (lib "Eletro-mechanical") (part "Nut"))
    )
    (comp (ref "NUT6")
      (value "M2.5")
      (footprint "BOSSARD_BN628-1241427_v")
      (description "Nut")
      (fields
        (field (name "PART NUMBER") "BOSSARD_BN628-1241427_v")
        (field (name "MANUFACTURER") "BOSSARD")
        (field (name "AUTHOR") "CERN DEM JMW")
      )
      (libsource (lib "Eletro-mechanical") (part "Nut"))
    )
    (comp (ref "NUT7")
      (value "M2.5")
      (footprint "BOSSARD_BN628-1241427_v")
      (description "Nut")
      (fields
        (field (name "PART NUMBER") "BOSSARD_BN628-1241427_v")
        (field (name "MANUFACTURER") "BOSSARD")
        (field (name "AUTHOR") "CERN DEM JMW")
      )
      (libsource (lib "Eletro-mechanical") (part "Nut"))
    )
    (comp (ref "NUT8")
      (value "M2.5")
      (footprint "BOSSARD_BN628-1241427_v")
      (description "Nut")
      (fields
        (field (name "PART NUMBER") "BOSSARD_BN628-1241427_v")
        (field (name "MANUFACTURER") "BOSSARD")
        (field (name "AUTHOR") "CERN DEM JMW")
      )
      (libsource (lib "Eletro-mechanical") (part "Nut"))
    )
    (comp (ref "NUT9")
      (value "M2.5")
      (footprint "BOSSARD_BN628-1241427_v")
      (description "Nut")
      (fields
        (field (name "PART NUMBER") "BOSSARD_BN628-1241427_v")
        (field (name "MANUFACTURER") "BOSSARD")
        (field (name "AUTHOR") "CERN DEM JMW")
      )
      (libsource (lib "Eletro-mechanical") (part "Nut"))
    )
    (comp (ref "NUT10")
      (value "M2.5")
      (footprint "BOSSARD_BN628-1241427_v")
      (description "Nut")
      (fields
        (field (name "PART NUMBER") "BOSSARD_BN628-1241427_v")
        (field (name "MANUFACTURER") "BOSSARD")
        (field (name "AUTHOR") "CERN DEM JMW")
      )
      (libsource (lib "Eletro-mechanical") (part "Nut"))
    )
    (comp (ref "NUT11")
      (value "M2.5")
      (footprint "BOSSARD_BN628-1241427_v")
      (description "Nut")
      (fields
        (field (name "PART NUMBER") "BOSSARD_BN628-1241427_v")
        (field (name "MANUFACTURER") "BOSSARD")
        (field (name "AUTHOR") "CERN DEM JMW")
      )
      (libsource (lib "Eletro-mechanical") (part "Nut"))
    )
    (comp (ref "NUT12")
      (value "M2.5")
      (footprint "BOSSARD_BN628-1241427_v")
      (description "Nut")
      (fields
        (field (name "PART NUMBER") "BOSSARD_BN628-1241427_v")
        (field (name "MANUFACTURER") "BOSSARD")
        (field (name "AUTHOR") "CERN DEM JMW")
      )
      (libsource (lib "Eletro-mechanical") (part "Nut"))
    )
    (comp (ref "NUT13")
      (value "M2.5")
      (footprint "BOSSARD_BN628-1241427_v")
      (description "Nut")
      (fields
        (field (name "PART NUMBER") "BOSSARD_BN628-1241427_v")
        (field (name "MANUFACTURER") "BOSSARD")
        (field (name "AUTHOR") "CERN DEM JMW")
      )
      (libsource (lib "Eletro-mechanical") (part "Nut"))
    )
    (comp (ref "SCREW1")
      (value "M2.5x4")
      (footprint "BOSSARD_BN5687-3061587_v")
      (description "Screw")
      (fields
        (field (name "PART NUMBER") "BOSSARD_BN5687-3061587_v")
        (field (name "MANUFACTURER") "BOSSARD")
        (field (name "AUTHOR") "CERN DEM JLC")
      )
      (libsource (lib "Eletro-mechanical") (part "Screw"))
    )
    (comp (ref "SCREW2")
      (value "M2.5x4")
      (footprint "BOSSARD_BN5687-3061587_v")
      (description "Screw")
      (fields
        (field (name "PART NUMBER") "BOSSARD_BN5687-3061587_v")
        (field (name "MANUFACTURER") "BOSSARD")
        (field (name "AUTHOR") "CERN DEM JLC")
      )
      (libsource (lib "Eletro-mechanical") (part "Screw"))
    )
    (comp (ref "SCREW3")
      (value "M2.5x10")
      (footprint "BOSSARD_B2.5X10/BN3333_v")
      (description "Screw; 2.5x10; Head: countersunk; Philips; A1 steel")
      (fields
        (field (name "PART NUMBER") "BOSSARD_B2.5X10/BN3333")
        (field (name "MANUFACTURER") "BOSSARD")
        (field (name "AUTHOR") "GK")
      )
      (libsource (lib "Mechanical") (part "Screw_M2.5x10_Countersunk_v"))
    )
    (comp (ref "SCREW4")
      (value "M2.5x10")
      (footprint "BOSSARD_B2.5X10/BN3333_v")
      (description "Screw; 2.5x10; Head: countersunk; Philips; A1 steel")
      (fields
        (field (name "PART NUMBER") "BOSSARD_B2.5X10/BN3333")
        (field (name "MANUFACTURER") "BOSSARD")
        (field (name "AUTHOR") "GK")
      )
      (libsource (lib "Mechanical") (part "Screw_M2.5x10_Countersunk_v"))
    )
    (comp (ref "SCREW5")
      (value "M2.5x10")
      (footprint "BOSSARD_B2.5X10/BN3333_v")
      (description "Screw; 2.5x10; Head: countersunk; Philips; A1 steel")
      (fields
        (field (name "PART NUMBER") "BOSSARD_B2.5X10/BN3333")
        (field (name "MANUFACTURER") "BOSSARD")
        (field (name "AUTHOR") "GK")
      )
      (libsource (lib "Mechanical") (part "Screw_M2.5x10_Countersunk_v"))
    )
    (comp (ref "SCREW6")
      (value "M2.5x10")
      (footprint "BOSSARD_B2.5X10/BN3333_v")
      (description "Screw; 2.5x10; Head: countersunk; Philips; A1 steel")
      (fields
        (field (name "PART NUMBER") "BOSSARD_B2.5X10/BN3333")
        (field (name "MANUFACTURER") "BOSSARD")
        (field (name "AUTHOR") "GK")
      )
      (libsource (lib "Mechanical") (part "Screw_M2.5x10_Countersunk_v"))
    )
    (comp (ref "SCREW7")
      (value "M2.5x10")
      (footprint "BOSSARD_B2.5X10/BN3333_v")
      (description "Screw; 2.5x10; Head: countersunk; Philips; A1 steel")
      (fields
        (field (name "PART NUMBER") "BOSSARD_B2.5X10/BN3333")
        (field (name "MANUFACTURER") "BOSSARD")
        (field (name "AUTHOR") "GK")
      )
      (libsource (lib "Mechanical") (part "Screw_M2.5x10_Countersunk_v"))
    )
    (comp (ref "SCREW8")
      (value "M2.5x10")
      (footprint "BOSSARD_B2.5X10/BN3333_v")
      (description "Screw; 2.5x10; Head: countersunk; Philips; A1 steel")
      (fields
        (field (name "PART NUMBER") "BOSSARD_B2.5X10/BN3333")
        (field (name "MANUFACTURER") "BOSSARD")
        (field (name "AUTHOR") "GK")
      )
      (libsource (lib "Mechanical") (part "Screw_M2.5x10_Countersunk_v"))
    )
    (comp (ref "SCREW9")
      (value "M2.5x10")
      (footprint "BOSSARD_B2.5X10/BN3333_v")
      (description "Screw; 2.5x10; Head: countersunk; Philips; A1 steel")
      (fields
        (field (name "PART NUMBER") "BOSSARD_B2.5X10/BN3333")
        (field (name "MANUFACTURER") "BOSSARD")
        (field (name "AUTHOR") "GK")
      )
      (libsource (lib "Mechanical") (part "Screw_M2.5x10_Countersunk_v"))
    )
    (comp (ref "SCREW10")
      (value "M2.5x10")
      (footprint "BOSSARD_B2.5X10/BN3333_v")
      (description "Screw; 2.5x10; Head: countersunk; Philips; A1 steel")
      (fields
        (field (name "PART NUMBER") "BOSSARD_B2.5X10/BN3333")
        (field (name "MANUFACTURER") "BOSSARD")
        (field (name "AUTHOR") "GK")
      )
      (libsource (lib "Mechanical") (part "Screw_M2.5x10_Countersunk_v"))
    )
    (comp (ref "SCREW11")
      (value "M2.5x10")
      (footprint "BOSSARD_B2.5X10/BN3333_v")
      (description "Screw; 2.5x10; Head: countersunk; Philips; A1 steel")
      (fields
        (field (name "PART NUMBER") "BOSSARD_B2.5X10/BN3333")
        (field (name "MANUFACTURER") "BOSSARD")
        (field (name "AUTHOR") "GK")
      )
      (libsource (lib "Mechanical") (part "Screw_M2.5x10_Countersunk_v"))
    )
    (comp (ref "SCREW12")
      (value "M2.5x4")
      (footprint "BOSSARD_BN5687-3061587_v")
      (description "Screw")
      (fields
        (field (name "PART NUMBER") "BOSSARD_BN5687-3061587_v")
        (field (name "MANUFACTURER") "BOSSARD")
        (field (name "AUTHOR") "CERN DEM JLC")
      )
      (libsource (lib "Eletro-mechanical") (part "Screw"))
    )
    (comp (ref "SCREW13")
      (value "M2.5x4")
      (footprint "BOSSARD_BN5687-3061587_v")
      (description "Screw")
      (fields
        (field (name "PART NUMBER") "BOSSARD_BN5687-3061587_v")
        (field (name "MANUFACTURER") "BOSSARD")
        (field (name "AUTHOR") "CERN DEM JLC")
      )
      (libsource (lib "Eletro-mechanical") (part "Screw"))
    )
    (comp (ref "ST2")
      (value "SCHROFF_PANEL_3U_8HP_HD68_BNC")
      (footprint "SCHROFF_PANEL_3HP_8U - HD68_BNC")
      (description "Schroff 8HP 3U EUROCARD Panel")
      (fields (field (name "MANUFACTURER") "Schroff") (field (name "MANUFACTURER PART NUMBER") "20849107"))
      (libsource (lib "Mechanical") (part "SCHROFF_PANEL_3U_8HP_HD68_BNC"))
    )
  )
  (nets
    (net (code "1") (name "/DAC_OUT_N1") (class "Default")
      (node (ref "J1") (pin "35") (pinfunction "35_35") (pintype "bidirectional"))
      (node (ref "J2") (pin "2") (pinfunction "2_2") (pintype "bidirectional"))
      (node (ref "J34") (pin "2") (pinfunction "2_2") (pintype "bidirectional"))
      (node (ref "J66") (pin "35") (pinfunction "35_35") (pintype "bidirectional"))
    )
    (net (code "2") (name "/DAC_OUT_N2") (class "Default")
      (node (ref "J1") (pin "36") (pinfunction "36_36") (pintype "bidirectional"))
      (node (ref "J36") (pin "2") (pinfunction "2_2") (pintype "bidirectional"))
      (node (ref "J4") (pin "2") (pinfunction "2_2") (pintype "bidirectional"))
      (node (ref "J66") (pin "36") (pinfunction "36_36") (pintype "bidirectional"))
    )
    (net (code "3") (name "/DAC_OUT_N3") (class "Default")
      (node (ref "J1") (pin "37") (pinfunction "37_37") (pintype "bidirectional"))
      (node (ref "J38") (pin "2") (pinfunction "2_2") (pintype "bidirectional"))
      (node (ref "J6") (pin "2") (pinfunction "2_2") (pintype "bidirectional"))
      (node (ref "J66") (pin "37") (pinfunction "37_37") (pintype "bidirectional"))
    )
    (net (code "4") (name "/DAC_OUT_N4") (class "Default")
      (node (ref "J1") (pin "38") (pinfunction "38_38") (pintype "bidirectional"))
      (node (ref "J40") (pin "2") (pinfunction "2_2") (pintype "bidirectional"))
      (node (ref "J66") (pin "38") (pinfunction "38_38") (pintype "bidirectional"))
      (node (ref "J8") (pin "2") (pinfunction "2_2") (pintype "bidirectional"))
    )
    (net (code "5") (name "/DAC_OUT_N5") (class "Default")
      (node (ref "J1") (pin "39") (pinfunction "39_39") (pintype "bidirectional"))
      (node (ref "J10") (pin "2") (pinfunction "2_2") (pintype "bidirectional"))
      (node (ref "J42") (pin "2") (pinfunction "2_2") (pintype "bidirectional"))
      (node (ref "J66") (pin "39") (pinfunction "39_39") (pintype "bidirectional"))
    )
    (net (code "6") (name "/DAC_OUT_N6") (class "Default")
      (node (ref "J1") (pin "40") (pinfunction "40_40") (pintype "bidirectional"))
      (node (ref "J12") (pin "2") (pinfunction "2_2") (pintype "bidirectional"))
      (node (ref "J44") (pin "2") (pinfunction "2_2") (pintype "bidirectional"))
      (node (ref "J66") (pin "40") (pinfunction "40_40") (pintype "bidirectional"))
    )
    (net (code "7") (name "/DAC_OUT_N7") (class "Default")
      (node (ref "J1") (pin "41") (pinfunction "41_41") (pintype "bidirectional"))
      (node (ref "J14") (pin "2") (pinfunction "2_2") (pintype "bidirectional"))
      (node (ref "J46") (pin "2") (pinfunction "2_2") (pintype "bidirectional"))
      (node (ref "J66") (pin "41") (pinfunction "41_41") (pintype "bidirectional"))
    )
    (net (code "8") (name "/DAC_OUT_N8") (class "Default")
      (node (ref "J1") (pin "42") (pinfunction "42_42") (pintype "bidirectional"))
      (node (ref "J16") (pin "2") (pinfunction "2_2") (pintype "bidirectional"))
      (node (ref "J48") (pin "2") (pinfunction "2_2") (pintype "bidirectional"))
      (node (ref "J66") (pin "42") (pinfunction "42_42") (pintype "bidirectional"))
    )
    (net (code "9") (name "/DAC_OUT_N9") (class "Default")
      (node (ref "J1") (pin "43") (pinfunction "43_43") (pintype "bidirectional"))
      (node (ref "J3") (pin "2") (pinfunction "2_2") (pintype "bidirectional"))
      (node (ref "J35") (pin "2") (pinfunction "2_2") (pintype "bidirectional"))
      (node (ref "J66") (pin "43") (pinfunction "43_43") (pintype "bidirectional"))
    )
    (net (code "10") (name "/DAC_OUT_N10") (class "Default")
      (node (ref "J1") (pin "44") (pinfunction "44_44") (pintype "bidirectional"))
      (node (ref "J37") (pin "2") (pinfunction "2_2") (pintype "bidirectional"))
      (node (ref "J5") (pin "2") (pinfunction "2_2") (pintype "bidirectional"))
      (node (ref "J66") (pin "44") (pinfunction "44_44") (pintype "bidirectional"))
    )
    (net (code "11") (name "/DAC_OUT_N11") (class "Default")
      (node (ref "J1") (pin "45") (pinfunction "45_45") (pintype "bidirectional"))
      (node (ref "J39") (pin "2") (pinfunction "2_2") (pintype "bidirectional"))
      (node (ref "J66") (pin "45") (pinfunction "45_45") (pintype "bidirectional"))
      (node (ref "J7") (pin "2") (pinfunction "2_2") (pintype "bidirectional"))
    )
    (net (code "12") (name "/DAC_OUT_N12") (class "Default")
      (node (ref "J1") (pin "46") (pinfunction "46_46") (pintype "bidirectional"))
      (node (ref "J41") (pin "2") (pinfunction "2_2") (pintype "bidirectional"))
      (node (ref "J66") (pin "46") (pinfunction "46_46") (pintype "bidirectional"))
      (node (ref "J9") (pin "2") (pinfunction "2_2") (pintype "bidirectional"))
    )
    (net (code "13") (name "/DAC_OUT_N13") (class "Default")
      (node (ref "J1") (pin "47") (pinfunction "47_47") (pintype "bidirectional"))
      (node (ref "J11") (pin "2") (pinfunction "2_2") (pintype "bidirectional"))
      (node (ref "J43") (pin "2") (pinfunction "2_2") (pintype "bidirectional"))
      (node (ref "J66") (pin "47") (pinfunction "47_47") (pintype "bidirectional"))
    )
    (net (code "14") (name "/DAC_OUT_N14") (class "Default")
      (node (ref "J1") (pin "48") (pinfunction "48_48") (pintype "bidirectional"))
      (node (ref "J13") (pin "2") (pinfunction "2_2") (pintype "bidirectional"))
      (node (ref "J45") (pin "2") (pinfunction "2_2") (pintype "bidirectional"))
      (node (ref "J66") (pin "48") (pinfunction "48_48") (pintype "bidirectional"))
    )
    (net (code "15") (name "/DAC_OUT_N15") (class "Default")
      (node (ref "J1") (pin "49") (pinfunction "49_49") (pintype "bidirectional"))
      (node (ref "J15") (pin "2") (pinfunction "2_2") (pintype "bidirectional"))
      (node (ref "J47") (pin "2") (pinfunction "2_2") (pintype "bidirectional"))
      (node (ref "J66") (pin "49") (pinfunction "49_49") (pintype "bidirectional"))
    )
    (net (code "16") (name "/DAC_OUT_N16") (class "Default")
      (node (ref "J1") (pin "50") (pinfunction "50_50") (pintype "bidirectional"))
      (node (ref "J17") (pin "2") (pinfunction "2_2") (pintype "bidirectional"))
      (node (ref "J49") (pin "2") (pinfunction "2_2") (pintype "bidirectional"))
      (node (ref "J66") (pin "50") (pinfunction "50_50") (pintype "bidirectional"))
    )
    (net (code "17") (name "/DAC_OUT_N17") (class "Default")
      (node (ref "J1") (pin "53") (pinfunction "53_53") (pintype "bidirectional"))
      (node (ref "J18") (pin "2") (pinfunction "2_2") (pintype "bidirectional"))
      (node (ref "J50") (pin "2") (pinfunction "2_2") (pintype "bidirectional"))
      (node (ref "J66") (pin "53") (pinfunction "53_53") (pintype "bidirectional"))
    )
    (net (code "18") (name "/DAC_OUT_N18") (class "Default")
      (node (ref "J1") (pin "54") (pinfunction "54_54") (pintype "bidirectional"))
      (node (ref "J20") (pin "2") (pinfunction "2_2") (pintype "bidirectional"))
      (node (ref "J52") (pin "2") (pinfunction "2_2") (pintype "bidirectional"))
      (node (ref "J66") (pin "54") (pinfunction "54_54") (pintype "bidirectional"))
    )
    (net (code "19") (name "/DAC_OUT_N19") (class "Default")
      (node (ref "J1") (pin "55") (pinfunction "55_55") (pintype "bidirectional"))
      (node (ref "J22") (pin "2") (pinfunction "2_2") (pintype "bidirectional"))
      (node (ref "J54") (pin "2") (pinfunction "2_2") (pintype "bidirectional"))
      (node (ref "J66") (pin "55") (pinfunction "55_55") (pintype "bidirectional"))
    )
    (net (code "20") (name "/DAC_OUT_N20") (class "Default")
      (node (ref "J1") (pin "56") (pinfunction "56_56") (pintype "bidirectional"))
      (node (ref "J24") (pin "2") (pinfunction "2_2") (pintype "bidirectional"))
      (node (ref "J56") (pin "2") (pinfunction "2_2") (pintype "bidirectional"))
      (node (ref "J66") (pin "56") (pinfunction "56_56") (pintype "bidirectional"))
    )
    (net (code "21") (name "/DAC_OUT_N21") (class "Default")
      (node (ref "J1") (pin "57") (pinfunction "57_57") (pintype "bidirectional"))
      (node (ref "J26") (pin "2") (pinfunction "2_2") (pintype "bidirectional"))
      (node (ref "J58") (pin "2") (pinfunction "2_2") (pintype "bidirectional"))
      (node (ref "J66") (pin "57") (pinfunction "57_57") (pintype "bidirectional"))
    )
    (net (code "22") (name "/DAC_OUT_N22") (class "Default")
      (node (ref "J1") (pin "58") (pinfunction "58_58") (pintype "bidirectional"))
      (node (ref "J28") (pin "2") (pinfunction "2_2") (pintype "bidirectional"))
      (node (ref "J60") (pin "2") (pinfunction "2_2") (pintype "bidirectional"))
      (node (ref "J66") (pin "58") (pinfunction "58_58") (pintype "bidirectional"))
    )
    (net (code "23") (name "/DAC_OUT_N23") (class "Default")
      (node (ref "J1") (pin "59") (pinfunction "59_59") (pintype "bidirectional"))
      (node (ref "J30") (pin "2") (pinfunction "2_2") (pintype "bidirectional"))
      (node (ref "J62") (pin "2") (pinfunction "2_2") (pintype "bidirectional"))
      (node (ref "J66") (pin "59") (pinfunction "59_59") (pintype "bidirectional"))
    )
    (net (code "24") (name "/DAC_OUT_N24") (class "Default")
      (node (ref "J1") (pin "60") (pinfunction "60_60") (pintype "bidirectional"))
      (node (ref "J32") (pin "2") (pinfunction "2_2") (pintype "bidirectional"))
      (node (ref "J64") (pin "2") (pinfunction "2_2") (pintype "bidirectional"))
      (node (ref "J66") (pin "60") (pinfunction "60_60") (pintype "bidirectional"))
    )
    (net (code "25") (name "/DAC_OUT_N25") (class "Default")
      (node (ref "J1") (pin "61") (pinfunction "61_61") (pintype "bidirectional"))
      (node (ref "J19") (pin "2") (pinfunction "2_2") (pintype "bidirectional"))
      (node (ref "J51") (pin "2") (pinfunction "2_2") (pintype "bidirectional"))
      (node (ref "J66") (pin "61") (pinfunction "61_61") (pintype "bidirectional"))
    )
    (net (code "26") (name "/DAC_OUT_N26") (class "Default")
      (node (ref "J1") (pin "62") (pinfunction "62_62") (pintype "bidirectional"))
      (node (ref "J21") (pin "2") (pinfunction "2_2") (pintype "bidirectional"))
      (node (ref "J53") (pin "2") (pinfunction "2_2") (pintype "bidirectional"))
      (node (ref "J66") (pin "62") (pinfunction "62_62") (pintype "bidirectional"))
    )
    (net (code "27") (name "/DAC_OUT_N27") (class "Default")
      (node (ref "J1") (pin "63") (pinfunction "63_63") (pintype "bidirectional"))
      (node (ref "J23") (pin "2") (pinfunction "2_2") (pintype "bidirectional"))
      (node (ref "J55") (pin "2") (pinfunction "2_2") (pintype "bidirectional"))
      (node (ref "J66") (pin "63") (pinfunction "63_63") (pintype "bidirectional"))
    )
    (net (code "28") (name "/DAC_OUT_N28") (class "Default")
      (node (ref "J1") (pin "64") (pinfunction "64_64") (pintype "bidirectional"))
      (node (ref "J25") (pin "2") (pinfunction "2_2") (pintype "bidirectional"))
      (node (ref "J57") (pin "2") (pinfunction "2_2") (pintype "bidirectional"))
      (node (ref "J66") (pin "64") (pinfunction "64_64") (pintype "bidirectional"))
    )
    (net (code "29") (name "/DAC_OUT_N29") (class "Default")
      (node (ref "J1") (pin "65") (pinfunction "65_65") (pintype "bidirectional"))
      (node (ref "J27") (pin "2") (pinfunction "2_2") (pintype "bidirectional"))
      (node (ref "J59") (pin "2") (pinfunction "2_2") (pintype "bidirectional"))
      (node (ref "J66") (pin "65") (pinfunction "65_65") (pintype "bidirectional"))
    )
    (net (code "30") (name "/DAC_OUT_N30") (class "Default")
      (node (ref "J1") (pin "66") (pinfunction "66_66") (pintype "bidirectional"))
      (node (ref "J29") (pin "2") (pinfunction "2_2") (pintype "bidirectional"))
      (node (ref "J61") (pin "2") (pinfunction "2_2") (pintype "bidirectional"))
      (node (ref "J66") (pin "66") (pinfunction "66_66") (pintype "bidirectional"))
    )
    (net (code "31") (name "/DAC_OUT_N31") (class "Default")
      (node (ref "J1") (pin "67") (pinfunction "67_67") (pintype "bidirectional"))
      (node (ref "J31") (pin "2") (pinfunction "2_2") (pintype "bidirectional"))
      (node (ref "J63") (pin "2") (pinfunction "2_2") (pintype "bidirectional"))
      (node (ref "J66") (pin "67") (pinfunction "67_67") (pintype "bidirectional"))
    )
    (net (code "32") (name "/DAC_OUT_N32") (class "Default")
      (node (ref "J1") (pin "68") (pinfunction "68_68") (pintype "bidirectional"))
      (node (ref "J33") (pin "2") (pinfunction "2_2") (pintype "bidirectional"))
      (node (ref "J65") (pin "2") (pinfunction "2_2") (pintype "bidirectional"))
      (node (ref "J66") (pin "68") (pinfunction "68_68") (pintype "bidirectional"))
    )
    (net (code "33") (name "/DAC_OUT_P1") (class "Default")
      (node (ref "J1") (pin "1") (pinfunction "1_1") (pintype "bidirectional"))
      (node (ref "J2") (pin "1") (pinfunction "1_1") (pintype "bidirectional"))
      (node (ref "J34") (pin "1") (pinfunction "1_1") (pintype "bidirectional"))
      (node (ref "J66") (pin "1") (pinfunction "1_1") (pintype "bidirectional"))
    )
    (net (code "34") (name "/DAC_OUT_P2") (class "Default")
      (node (ref "J1") (pin "2") (pinfunction "2_2") (pintype "bidirectional"))
      (node (ref "J36") (pin "1") (pinfunction "1_1") (pintype "bidirectional"))
      (node (ref "J4") (pin "1") (pinfunction "1_1") (pintype "bidirectional"))
      (node (ref "J66") (pin "2") (pinfunction "2_2") (pintype "bidirectional"))
    )
    (net (code "35") (name "/DAC_OUT_P3") (class "Default")
      (node (ref "J1") (pin "3") (pinfunction "3_3") (pintype "bidirectional"))
      (node (ref "J38") (pin "1") (pinfunction "1_1") (pintype "bidirectional"))
      (node (ref "J6") (pin "1") (pinfunction "1_1") (pintype "bidirectional"))
      (node (ref "J66") (pin "3") (pinfunction "3_3") (pintype "bidirectional"))
    )
    (net (code "36") (name "/DAC_OUT_P4") (class "Default")
      (node (ref "J1") (pin "4") (pinfunction "4_4") (pintype "bidirectional"))
      (node (ref "J40") (pin "1") (pinfunction "1_1") (pintype "bidirectional"))
      (node (ref "J66") (pin "4") (pinfunction "4_4") (pintype "bidirectional"))
      (node (ref "J8") (pin "1") (pinfunction "1_1") (pintype "bidirectional"))
    )
    (net (code "37") (name "/DAC_OUT_P5") (class "Default")
      (node (ref "J1") (pin "5") (pinfunction "5_5") (pintype "bidirectional"))
      (node (ref "J10") (pin "1") (pinfunction "1_1") (pintype "bidirectional"))
      (node (ref "J42") (pin "1") (pinfunction "1_1") (pintype "bidirectional"))
      (node (ref "J66") (pin "5") (pinfunction "5_5") (pintype "bidirectional"))
    )
    (net (code "38") (name "/DAC_OUT_P6") (class "Default")
      (node (ref "J1") (pin "6") (pinfunction "6_6") (pintype "bidirectional"))
      (node (ref "J12") (pin "1") (pinfunction "1_1") (pintype "bidirectional"))
      (node (ref "J44") (pin "1") (pinfunction "1_1") (pintype "bidirectional"))
      (node (ref "J66") (pin "6") (pinfunction "6_6") (pintype "bidirectional"))
    )
    (net (code "39") (name "/DAC_OUT_P7") (class "Default")
      (node (ref "J1") (pin "7") (pinfunction "7_7") (pintype "bidirectional"))
      (node (ref "J14") (pin "1") (pinfunction "1_1") (pintype "bidirectional"))
      (node (ref "J46") (pin "1") (pinfunction "1_1") (pintype "bidirectional"))
      (node (ref "J66") (pin "7") (pinfunction "7_7") (pintype "bidirectional"))
    )
    (net (code "40") (name "/DAC_OUT_P8") (class "Default")
      (node (ref "J1") (pin "8") (pinfunction "8_8") (pintype "bidirectional"))
      (node (ref "J16") (pin "1") (pinfunction "1_1") (pintype "bidirectional"))
      (node (ref "J48") (pin "1") (pinfunction "1_1") (pintype "bidirectional"))
      (node (ref "J66") (pin "8") (pinfunction "8_8") (pintype "bidirectional"))
    )
    (net (code "41") (name "/DAC_OUT_P9") (class "Default")
      (node (ref "J1") (pin "9") (pinfunction "9_9") (pintype "bidirectional"))
      (node (ref "J3") (pin "1") (pinfunction "1_1") (pintype "bidirectional"))
      (node (ref "J35") (pin "1") (pinfunction "1_1") (pintype "bidirectional"))
      (node (ref "J66") (pin "9") (pinfunction "9_9") (pintype "bidirectional"))
    )
    (net (code "42") (name "/DAC_OUT_P10") (class "Default")
      (node (ref "J1") (pin "10") (pinfunction "10_10") (pintype "bidirectional"))
      (node (ref "J37") (pin "1") (pinfunction "1_1") (pintype "bidirectional"))
      (node (ref "J5") (pin "1") (pinfunction "1_1") (pintype "bidirectional"))
      (node (ref "J66") (pin "10") (pinfunction "10_10") (pintype "bidirectional"))
    )
    (net (code "43") (name "/DAC_OUT_P11") (class "Default")
      (node (ref "J1") (pin "11") (pinfunction "11_11") (pintype "bidirectional"))
      (node (ref "J39") (pin "1") (pinfunction "1_1") (pintype "bidirectional"))
      (node (ref "J66") (pin "11") (pinfunction "11_11") (pintype "bidirectional"))
      (node (ref "J7") (pin "1") (pinfunction "1_1") (pintype "bidirectional"))
    )
    (net (code "44") (name "/DAC_OUT_P12") (class "Default")
      (node (ref "J1") (pin "12") (pinfunction "12_12") (pintype "bidirectional"))
      (node (ref "J41") (pin "1") (pinfunction "1_1") (pintype "bidirectional"))
      (node (ref "J66") (pin "12") (pinfunction "12_12") (pintype "bidirectional"))
      (node (ref "J9") (pin "1") (pinfunction "1_1") (pintype "bidirectional"))
    )
    (net (code "45") (name "/DAC_OUT_P13") (class "Default")
      (node (ref "J1") (pin "13") (pinfunction "13_13") (pintype "bidirectional"))
      (node (ref "J11") (pin "1") (pinfunction "1_1") (pintype "bidirectional"))
      (node (ref "J43") (pin "1") (pinfunction "1_1") (pintype "bidirectional"))
      (node (ref "J66") (pin "13") (pinfunction "13_13") (pintype "bidirectional"))
    )
    (net (code "46") (name "/DAC_OUT_P14") (class "Default")
      (node (ref "J1") (pin "14") (pinfunction "14_14") (pintype "bidirectional"))
      (node (ref "J13") (pin "1") (pinfunction "1_1") (pintype "bidirectional"))
      (node (ref "J45") (pin "1") (pinfunction "1_1") (pintype "bidirectional"))
      (node (ref "J66") (pin "14") (pinfunction "14_14") (pintype "bidirectional"))
    )
    (net (code "47") (name "/DAC_OUT_P15") (class "Default")
      (node (ref "J1") (pin "15") (pinfunction "15_15") (pintype "bidirectional"))
      (node (ref "J15") (pin "1") (pinfunction "1_1") (pintype "bidirectional"))
      (node (ref "J47") (pin "1") (pinfunction "1_1") (pintype "bidirectional"))
      (node (ref "J66") (pin "15") (pinfunction "15_15") (pintype "bidirectional"))
    )
    (net (code "48") (name "/DAC_OUT_P16") (class "Default")
      (node (ref "J1") (pin "16") (pinfunction "16_16") (pintype "bidirectional"))
      (node (ref "J17") (pin "1") (pinfunction "1_1") (pintype "bidirectional"))
      (node (ref "J49") (pin "1") (pinfunction "1_1") (pintype "bidirectional"))
      (node (ref "J66") (pin "16") (pinfunction "16_16") (pintype "bidirectional"))
    )
    (net (code "49") (name "/DAC_OUT_P17") (class "Default")
      (node (ref "J1") (pin "19") (pinfunction "19_19") (pintype "bidirectional"))
      (node (ref "J18") (pin "1") (pinfunction "1_1") (pintype "bidirectional"))
      (node (ref "J50") (pin "1") (pinfunction "1_1") (pintype "bidirectional"))
      (node (ref "J66") (pin "19") (pinfunction "19_19") (pintype "bidirectional"))
    )
    (net (code "50") (name "/DAC_OUT_P18") (class "Default")
      (node (ref "J1") (pin "20") (pinfunction "20_20") (pintype "bidirectional"))
      (node (ref "J20") (pin "1") (pinfunction "1_1") (pintype "bidirectional"))
      (node (ref "J52") (pin "1") (pinfunction "1_1") (pintype "bidirectional"))
      (node (ref "J66") (pin "20") (pinfunction "20_20") (pintype "bidirectional"))
    )
    (net (code "51") (name "/DAC_OUT_P19") (class "Default")
      (node (ref "J1") (pin "21") (pinfunction "21_21") (pintype "bidirectional"))
      (node (ref "J22") (pin "1") (pinfunction "1_1") (pintype "bidirectional"))
      (node (ref "J54") (pin "1") (pinfunction "1_1") (pintype "bidirectional"))
      (node (ref "J66") (pin "21") (pinfunction "21_21") (pintype "bidirectional"))
    )
    (net (code "52") (name "/DAC_OUT_P20") (class "Default")
      (node (ref "J1") (pin "22") (pinfunction "22_22") (pintype "bidirectional"))
      (node (ref "J24") (pin "1") (pinfunction "1_1") (pintype "bidirectional"))
      (node (ref "J56") (pin "1") (pinfunction "1_1") (pintype "bidirectional"))
      (node (ref "J66") (pin "22") (pinfunction "22_22") (pintype "bidirectional"))
    )
    (net (code "53") (name "/DAC_OUT_P21") (class "Default")
      (node (ref "J1") (pin "23") (pinfunction "23_23") (pintype "bidirectional"))
      (node (ref "J26") (pin "1") (pinfunction "1_1") (pintype "bidirectional"))
      (node (ref "J58") (pin "1") (pinfunction "1_1") (pintype "bidirectional"))
      (node (ref "J66") (pin "23") (pinfunction "23_23") (pintype "bidirectional"))
    )
    (net (code "54") (name "/DAC_OUT_P22") (class "Default")
      (node (ref "J1") (pin "24") (pinfunction "24_24") (pintype "bidirectional"))
      (node (ref "J28") (pin "1") (pinfunction "1_1") (pintype "bidirectional"))
      (node (ref "J60") (pin "1") (pinfunction "1_1") (pintype "bidirectional"))
      (node (ref "J66") (pin "24") (pinfunction "24_24") (pintype "bidirectional"))
    )
    (net (code "55") (name "/DAC_OUT_P23") (class "Default")
      (node (ref "J1") (pin "25") (pinfunction "25_25") (pintype "bidirectional"))
      (node (ref "J30") (pin "1") (pinfunction "1_1") (pintype "bidirectional"))
      (node (ref "J62") (pin "1") (pinfunction "1_1") (pintype "bidirectional"))
      (node (ref "J66") (pin "25") (pinfunction "25_25") (pintype "bidirectional"))
    )
    (net (code "56") (name "/DAC_OUT_P24") (class "Default")
      (node (ref "J1") (pin "26") (pinfunction "26_26") (pintype "bidirectional"))
      (node (ref "J32") (pin "1") (pinfunction "1_1") (pintype "bidirectional"))
      (node (ref "J64") (pin "1") (pinfunction "1_1") (pintype "bidirectional"))
      (node (ref "J66") (pin "26") (pinfunction "26_26") (pintype "bidirectional"))
    )
    (net (code "57") (name "/DAC_OUT_P25") (class "Default")
      (node (ref "J1") (pin "27") (pinfunction "27_27") (pintype "bidirectional"))
      (node (ref "J19") (pin "1") (pinfunction "1_1") (pintype "bidirectional"))
      (node (ref "J51") (pin "1") (pinfunction "1_1") (pintype "bidirectional"))
      (node (ref "J66") (pin "27") (pinfunction "27_27") (pintype "bidirectional"))
    )
    (net (code "58") (name "/DAC_OUT_P26") (class "Default")
      (node (ref "J1") (pin "28") (pinfunction "28_28") (pintype "bidirectional"))
      (node (ref "J21") (pin "1") (pinfunction "1_1") (pintype "bidirectional"))
      (node (ref "J53") (pin "1") (pinfunction "1_1") (pintype "bidirectional"))
      (node (ref "J66") (pin "28") (pinfunction "28_28") (pintype "bidirectional"))
    )
    (net (code "59") (name "/DAC_OUT_P27") (class "Default")
      (node (ref "J1") (pin "29") (pinfunction "29_29") (pintype "bidirectional"))
      (node (ref "J23") (pin "1") (pinfunction "1_1") (pintype "bidirectional"))
      (node (ref "J55") (pin "1") (pinfunction "1_1") (pintype "bidirectional"))
      (node (ref "J66") (pin "29") (pinfunction "29_29") (pintype "bidirectional"))
    )
    (net (code "60") (name "/DAC_OUT_P28") (class "Default")
      (node (ref "J1") (pin "30") (pinfunction "30_30") (pintype "bidirectional"))
      (node (ref "J25") (pin "1") (pinfunction "1_1") (pintype "bidirectional"))
      (node (ref "J57") (pin "1") (pinfunction "1_1") (pintype "bidirectional"))
      (node (ref "J66") (pin "30") (pinfunction "30_30") (pintype "bidirectional"))
    )
    (net (code "61") (name "/DAC_OUT_P29") (class "Default")
      (node (ref "J1") (pin "31") (pinfunction "31_31") (pintype "bidirectional"))
      (node (ref "J27") (pin "1") (pinfunction "1_1") (pintype "bidirectional"))
      (node (ref "J59") (pin "1") (pinfunction "1_1") (pintype "bidirectional"))
      (node (ref "J66") (pin "31") (pinfunction "31_31") (pintype "bidirectional"))
    )
    (net (code "62") (name "/DAC_OUT_P30") (class "Default")
      (node (ref "J1") (pin "32") (pinfunction "32_32") (pintype "bidirectional"))
      (node (ref "J29") (pin "1") (pinfunction "1_1") (pintype "bidirectional"))
      (node (ref "J61") (pin "1") (pinfunction "1_1") (pintype "bidirectional"))
      (node (ref "J66") (pin "32") (pinfunction "32_32") (pintype "bidirectional"))
    )
    (net (code "63") (name "/DAC_OUT_P31") (class "Default")
      (node (ref "J1") (pin "33") (pinfunction "33_33") (pintype "bidirectional"))
      (node (ref "J31") (pin "1") (pinfunction "1_1") (pintype "bidirectional"))
      (node (ref "J63") (pin "1") (pinfunction "1_1") (pintype "bidirectional"))
      (node (ref "J66") (pin "33") (pinfunction "33_33") (pintype "bidirectional"))
    )
    (net (code "64") (name "/DAC_OUT_P32") (class "Default")
      (node (ref "J1") (pin "34") (pinfunction "34_34") (pintype "bidirectional"))
      (node (ref "J33") (pin "1") (pinfunction "1_1") (pintype "bidirectional"))
      (node (ref "J65") (pin "1") (pinfunction "1_1") (pintype "bidirectional"))
      (node (ref "J66") (pin "34") (pinfunction "34_34") (pintype "bidirectional"))
    )
    (net (code "65") (name "GND") (class "Default")
      (node (ref "B1") (pin "1") (pinfunction "1_1") (pintype "bidirectional"))
      (node (ref "B2") (pin "1") (pinfunction "1_1") (pintype "bidirectional"))
      (node (ref "B3") (pin "1") (pinfunction "1_1") (pintype "bidirectional"))
      (node (ref "B4") (pin "1") (pinfunction "1_1") (pintype "bidirectional"))
      (node (ref "B7") (pin "1") (pinfunction "1_1") (pintype "bidirectional"))
      (node (ref "B8") (pin "1") (pinfunction "1_1") (pintype "bidirectional"))
      (node (ref "B9") (pin "1") (pinfunction "1_1") (pintype "bidirectional"))
      (node (ref "J1") (pin "17") (pinfunction "17_17") (pintype "bidirectional"))
      (node (ref "J1") (pin "51") (pinfunction "51_51") (pintype "bidirectional"))
      (node (ref "J1") (pin "69") (pinfunction "69_69") (pintype "bidirectional"))
      (node (ref "J1") (pin "70") (pinfunction "70_70") (pintype "bidirectional"))
      (node (ref "J66") (pin "17") (pinfunction "17_17") (pintype "bidirectional"))
      (node (ref "J66") (pin "51") (pinfunction "51_51") (pintype "bidirectional"))
      (node (ref "J66") (pin "69") (pinfunction "69_69") (pintype "passive"))
      (node (ref "J66") (pin "70") (pinfunction "70_70") (pintype "passive"))
      (node (ref "ST2") (pin "0") (pinfunction "0_0") (pintype "passive"))
      (node (ref "ST2") (pin "1") (pinfunction "1_1") (pintype "passive"))
    )
    (net (code "66") (name "N13V0_SCSI") (class "Default")
      (node (ref "J1") (pin "52") (pinfunction "52_52") (pintype "bidirectional"))
      (node (ref "J66") (pin "52") (pinfunction "52_52") (pintype "bidirectional"))
    )
    (net (code "67") (name "P13V0_SCSI") (class "Default")
      (node (ref "J1") (pin "18") (pinfunction "18_18") (pintype "bidirectional"))
      (node (ref "J66") (pin "18") (pinfunction "18_18") (pintype "bidirectional"))
    )
  )
)
